# GD_interface.net
KiCad netlist of a schematic drawn in Altium Designer
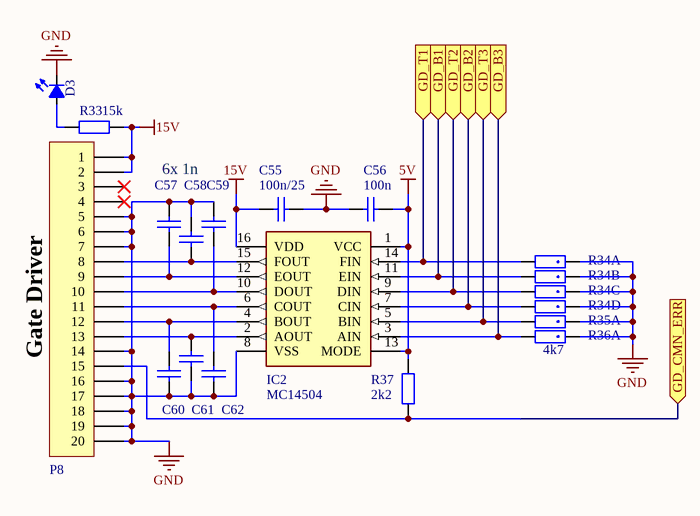
[diagram p0: GD_interface.SchDoc]

(export (version "E")
  (design (tool "Eeschema 10.0.6"))
  (components
    (comp (ref "C55")
      (value "100n/25")
      (footprint "C_0603")
      (description "cond")
      (libsource (lib "M_Standard") (part "C_MLCC"))
    )
    (comp (ref "C56")
      (value "100n")
      (footprint "C_0603")
      (description "cond")
      (libsource (lib "M_Standard") (part "C_MLCC"))
    )
    (comp (ref "C57")
      (value "1n")
      (footprint "C_0603")
      (description "cond")
      (libsource (lib "M_Standard") (part "C_MLCC"))
    )
    (comp (ref "C58")
      (value "1n")
      (footprint "C_0603")
      (description "cond")
      (libsource (lib "M_Standard") (part "C_MLCC"))
    )
    (comp (ref "C59")
      (value "1n")
      (footprint "C_0603")
      (description "cond")
      (libsource (lib "M_Standard") (part "C_MLCC"))
    )
    (comp (ref "C60")
      (value "1n")
      (footprint "C_0603")
      (description "cond")
      (libsource (lib "M_Standard") (part "C_MLCC"))
    )
    (comp (ref "C61")
      (value "1n")
      (footprint "C_0603")
      (description "cond")
      (libsource (lib "M_Standard") (part "C_MLCC"))
    )
    (comp (ref "C62")
      (value "1n")
      (footprint "C_0603")
      (description "cond")
      (libsource (lib "M_Standard") (part "C_MLCC"))
    )
    (comp (ref "D3")
      (value "Green")
      (footprint "D0603")
      (description "LED diode")
      (libsource (lib "M_Standard") (part "D_LED small"))
    )
    (comp (ref "IC2")
      (value "MC14504")
      (footprint "SOP65P640X120-16N")
      (description "Level shifter")
      (fields
        (field (name "MANUFACTURER_PART_NUMBER") "MC14504BDTG")
        (field (name "MOUSER PART NUMBER") "863-MC14504BDTG")
      )
      (libsource (lib "M_Standard") (part "IC_MC14504"))
    )
    (comp (ref "P8")
      (value "GD")
      (footprint "TE_MicroMatch_20_SMD_Female")
      (description "Te connectivity Micro Match: 2-338069-0")
      (fields (field (name "MANUFACTURER") "Tyco"))
      (libsource (lib "Miscellaneous Connectors") (part "Header 20"))
    )
    (comp (ref "R33")
      (value "15k")
      (footprint "R_0603")
      (description "Resistor")
      (libsource (lib "M_Standard") (part "R_Uni"))
    )
    (comp (ref "R34")
      (value "1k")
      (footprint "R_Array  4D03")
      (description "Resistor array 4xR,  size 1206, 64mW")
      (libsource (lib "M_Standard") (part "R_Array 4xR"))
    )
    (comp (ref "R35")
      (value "1k")
      (footprint "R_Array  4D03")
      (description "Resistor array 4xR,  size 1206, 64mW")
      (libsource (lib "M_Standard") (part "R_Array 4xR"))
    )
    (comp (ref "R36")
      (value "4k7")
      (footprint "R_Array  4D03")
      (description "Resistor array 4xR,  size 1206, 64mW")
      (libsource (lib "M_Standard") (part "R_Array 4xR"))
    )
    (comp (ref "R37")
      (value "2k2")
      (footprint "R_0603")
      (description "Resistor")
      (libsource (lib "") (part "R_Uni_1"))
    )
  )
  (nets
    (net (code "1") (name "/GD_B1") (class "Default")
      (node (ref "IC2") (pin "11") (pinfunction "EIN_11") (pintype "input"))
      (node (ref "R34") (pin "7") (pinfunction "7_7") (pintype "passive"))
    )
    (net (code "2") (name "/GD_B2") (class "Default")
      (node (ref "IC2") (pin "7") (pinfunction "CIN_7") (pintype "input"))
      (node (ref "R34") (pin "5") (pinfunction "5_5") (pintype "passive"))
    )
    (net (code "3") (name "/GD_B3") (class "Default")
      (node (ref "IC2") (pin "3") (pinfunction "AIN_3") (pintype "input"))
      (node (ref "R36") (pin "8") (pinfunction "8_8") (pintype "passive"))
    )
    (net (code "4") (name "/GD_CMN_ERR") (class "Default")
      (node (ref "P8") (pin "15") (pinfunction "15_15") (pintype "passive"))
      (node (ref "R37") (pin "2") (pinfunction "2_2") (pintype "passive"))
    )
    (net (code "5") (name "/GD_T1") (class "Default")
      (node (ref "IC2") (pin "14") (pinfunction "FIN_14") (pintype "input"))
      (node (ref "R34") (pin "8") (pinfunction "8_8") (pintype "passive"))
    )
    (net (code "6") (name "/GD_T2") (class "Default")
      (node (ref "IC2") (pin "9") (pinfunction "DIN_9") (pintype "input"))
      (node (ref "R34") (pin "6") (pinfunction "6_6") (pintype "passive"))
    )
    (net (code "7") (name "/GD_T3") (class "Default")
      (node (ref "IC2") (pin "5") (pinfunction "BIN_5") (pintype "input"))
      (node (ref "R35") (pin "8") (pinfunction "8_8") (pintype "passive"))
    )
    (net (code "8") (name "5V") (class "Default")
      (node (ref "C56") (pin "2") (pinfunction "2_2") (pintype "passive"))
      (node (ref "IC2") (pin "1") (pinfunction "VCC_1") (pintype "power_in"))
      (node (ref "IC2") (pin "13") (pinfunction "MODE_13") (pintype "passive"))
      (node (ref "R37") (pin "1") (pinfunction "1_1") (pintype "passive"))
    )
    (net (code "9") (name "15V") (class "Default")
      (node (ref "C55") (pin "1") (pinfunction "1_1") (pintype "passive"))
      (node (ref "IC2") (pin "16") (pinfunction "VDD_16") (pintype "power_in"))
      (node (ref "P8") (pin "1") (pinfunction "1_1") (pintype "passive"))
      (node (ref "P8") (pin "2") (pinfunction "2_2") (pintype "passive"))
      (node (ref "R33") (pin "2") (pinfunction "2_2") (pintype "passive"))
    )
    (net (code "10") (name "GND") (class "Default")
      (node (ref "C55") (pin "2") (pinfunction "2_2") (pintype "passive"))
      (node (ref "C56") (pin "1") (pinfunction "1_1") (pintype "passive"))
      (node (ref "C57") (pin "2") (pinfunction "2_2") (pintype "passive"))
      (node (ref "C58") (pin "2") (pinfunction "2_2") (pintype "passive"))
      (node (ref "C59") (pin "2") (pinfunction "2_2") (pintype "passive"))
      (node (ref "C60") (pin "1") (pinfunction "1_1") (pintype "passive"))
      (node (ref "C61") (pin "1") (pinfunction "1_1") (pintype "passive"))
      (node (ref "C62") (pin "1") (pinfunction "1_1") (pintype "passive"))
      (node (ref "D3") (pin "1") (pinfunction "K_1") (pintype "passive"))
      (node (ref "IC2") (pin "8") (pinfunction "VSS_8") (pintype "power_in"))
      (node (ref "P8") (pin "14") (pinfunction "14_14") (pintype "passive"))
      (node (ref "P8") (pin "16") (pinfunction "16_16") (pintype "passive"))
      (node (ref "P8") (pin "17") (pinfunction "17_17") (pintype "passive"))
      (node (ref "P8") (pin "18") (pinfunction "18_18") (pintype "passive"))
      (node (ref "P8") (pin "19") (pinfunction "19_19") (pintype "passive"))
      (node (ref "P8") (pin "20") (pinfunction "20_20") (pintype "passive"))
      (node (ref "P8") (pin "5") (pinfunction "5_5") (pintype "passive"))
      (node (ref "P8") (pin "6") (pinfunction "6_6") (pintype "passive"))
      (node (ref "P8") (pin "7") (pinfunction "7_7") (pintype "passive"))
      (node (ref "R34") (pin "1") (pinfunction "1_1") (pintype "passive"))
      (node (ref "R34") (pin "2") (pinfunction "2_2") (pintype "passive"))
      (node (ref "R34") (pin "3") (pinfunction "3_3") (pintype "passive"))
      (node (ref "R34") (pin "4") (pinfunction "4_4") (pintype "passive"))
      (node (ref "R35") (pin "1") (pinfunction "1_1") (pintype "passive"))
      (node (ref "R36") (pin "1") (pinfunction "1_1") (pintype "passive"))
    )
    (net (code "11") (name "Net-(D3-A)") (class "Default")
      (node (ref "D3") (pin "2") (pinfunction "A_2") (pintype "passive"))
      (node (ref "R33") (pin "1") (pinfunction "1_1") (pintype "passive"))
    )
    (net (code "12") (name "Net-(IC2-AOUT)") (class "Default")
      (node (ref "C62") (pin "2") (pinfunction "2_2") (pintype "passive"))
      (node (ref "IC2") (pin "2") (pinfunction "AOUT_2") (pintype "output"))
      (node (ref "P8") (pin "13") (pinfunction "13_13") (pintype "passive"))
    )
    (net (code "13") (name "Net-(IC2-BOUT)") (class "Default")
      (node (ref "C60") (pin "2") (pinfunction "2_2") (pintype "passive"))
      (node (ref "IC2") (pin "4") (pinfunction "BOUT_4") (pintype "output"))
      (node (ref "P8") (pin "12") (pinfunction "12_12") (pintype "passive"))
    )
    (net (code "14") (name "Net-(IC2-COUT)") (class "Default")
      (node (ref "C61") (pin "2") (pinfunction "2_2") (pintype "passive"))
      (node (ref "IC2") (pin "6") (pinfunction "COUT_6") (pintype "output"))
      (node (ref "P8") (pin "11") (pinfunction "11_11") (pintype "passive"))
    )
    (net (code "15") (name "Net-(IC2-DOUT)") (class "Default")
      (node (ref "C59") (pin "1") (pinfunction "1_1") (pintype "passive"))
      (node (ref "IC2") (pin "10") (pinfunction "DOUT_10") (pintype "output"))
      (node (ref "P8") (pin "10") (pinfunction "10_10") (pintype "passive"))
    )
    (net (code "16") (name "Net-(IC2-EOUT)") (class "Default")
      (node (ref "C57") (pin "1") (pinfunction "1_1") (pintype "passive"))
      (node (ref "IC2") (pin "12") (pinfunction "EOUT_12") (pintype "output"))
      (node (ref "P8") (pin "9") (pinfunction "9_9") (pintype "passive"))
    )
    (net (code "17") (name "Net-(IC2-FOUT)") (class "Default")
      (node (ref "C58") (pin "1") (pinfunction "1_1") (pintype "passive"))
      (node (ref "IC2") (pin "15") (pinfunction "FOUT_15") (pintype "output"))
      (node (ref "P8") (pin "8") (pinfunction "8_8") (pintype "passive"))
    )
    (net (code "18") (name "unconnected-(P8-Pad3)") (class "Default")
      (node (ref "P8") (pin "3") (pinfunction "3_3") (pintype "passive+no_connect"))
    )
    (net (code "19") (name "unconnected-(P8-Pad4)") (class "Default")
      (node (ref "P8") (pin "4") (pinfunction "4_4") (pintype "passive+no_connect"))
    )
  )
)
